# FPGA_7A35T_POWER.net
KiCad netlist of a schematic drawn in Altium Designer
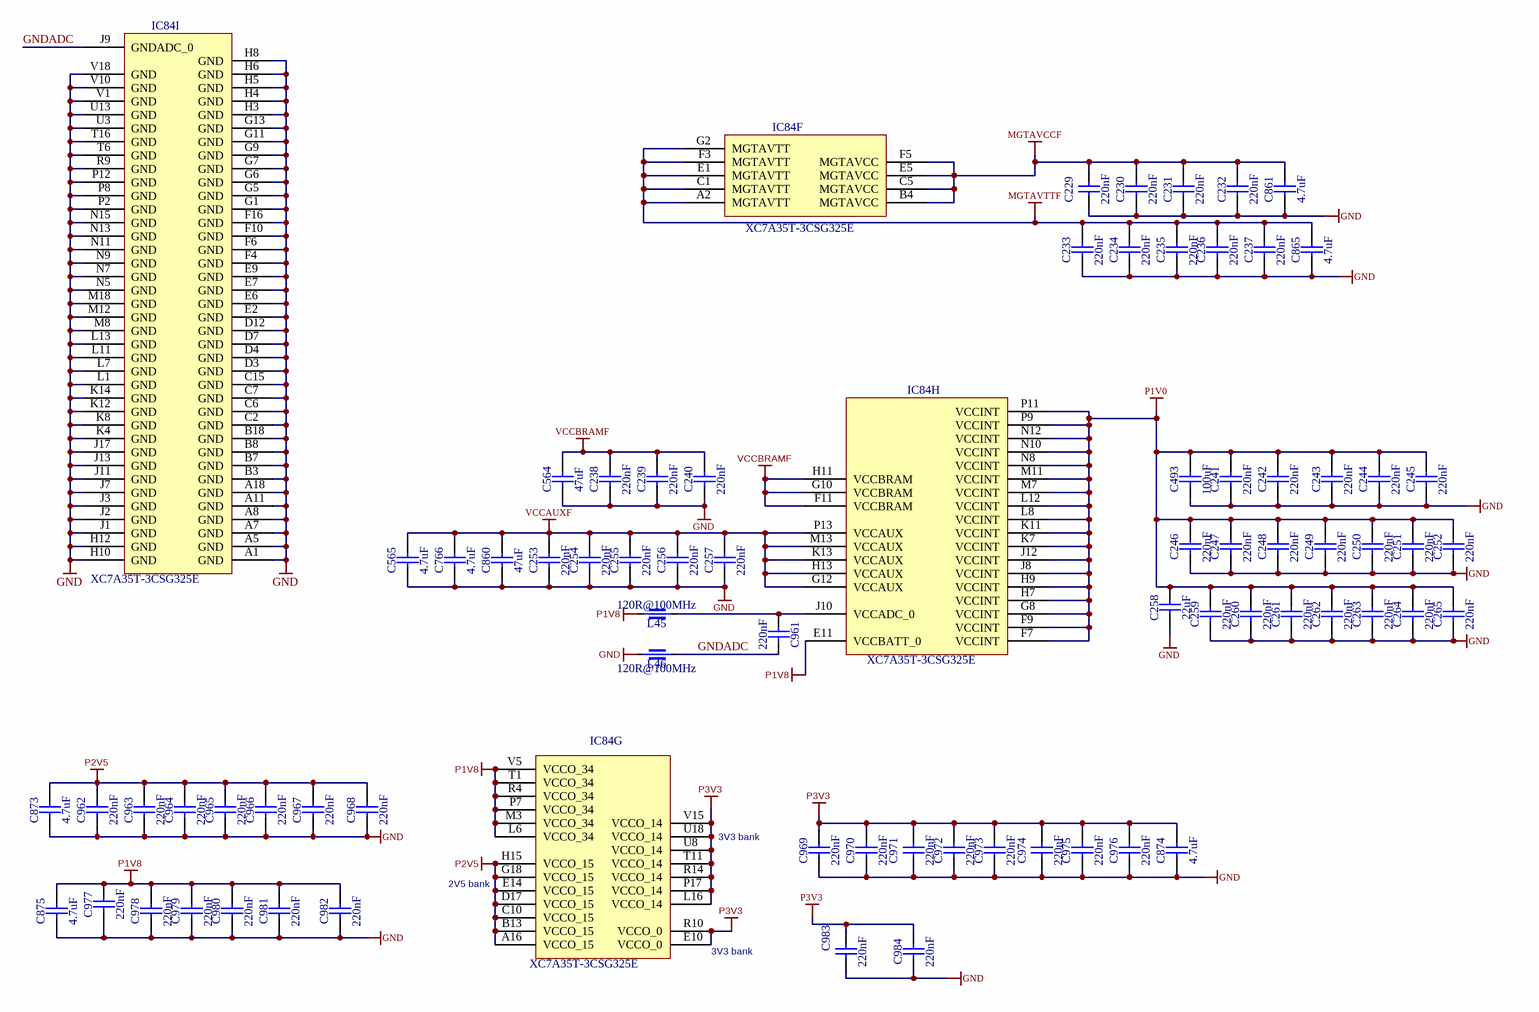
[diagram p0: FPGA_7A35T_POWER.SchDoc]

(export (version "E")
  (design (tool "Eeschema 10.0.6"))
  (components
    (comp (ref "C229")
      (value "220nF")
      (footprint "CAPC0603X33N")
      (description "Non-polarised capacitor")
      (fields
        (field (name "MANUFACTURER PART NUMBER") "CC0201_220NF_6.3V_20%_X5R")
        (field (name "MANUFACTURER") "GENERIC")
        (field (name "AUTHOR") "CERN DEM JLC")
      )
      (libsource (lib "Capacitors") (part "Capacitor - non polarized"))
    )
    (comp (ref "C230")
      (value "220nF")
      (footprint "CAPC0603X33N")
      (description "Non-polarised capacitor")
      (fields
        (field (name "MANUFACTURER PART NUMBER") "CC0201_220NF_6.3V_20%_X5R")
        (field (name "MANUFACTURER") "GENERIC")
        (field (name "AUTHOR") "CERN DEM JLC")
      )
      (libsource (lib "Capacitors") (part "Capacitor - non polarized"))
    )
    (comp (ref "C231")
      (value "220nF")
      (footprint "CAPC0603X33N")
      (description "Non-polarised capacitor")
      (fields
        (field (name "MANUFACTURER PART NUMBER") "CC0201_220NF_6.3V_20%_X5R")
        (field (name "MANUFACTURER") "GENERIC")
        (field (name "AUTHOR") "CERN DEM JLC")
      )
      (libsource (lib "Capacitors") (part "Capacitor - non polarized"))
    )
    (comp (ref "C232")
      (value "220nF")
      (footprint "CAPC0603X33N")
      (description "Non-polarised capacitor")
      (fields
        (field (name "MANUFACTURER PART NUMBER") "CC0201_220NF_6.3V_20%_X5R")
        (field (name "MANUFACTURER") "GENERIC")
        (field (name "AUTHOR") "CERN DEM JLC")
      )
      (libsource (lib "Capacitors") (part "Capacitor - non polarized"))
    )
    (comp (ref "C233")
      (value "220nF")
      (footprint "CAPC0603X33N")
      (description "Non-polarised capacitor")
      (fields
        (field (name "MANUFACTURER PART NUMBER") "CC0201_220NF_6.3V_20%_X5R")
        (field (name "MANUFACTURER") "GENERIC")
        (field (name "AUTHOR") "CERN DEM JLC")
      )
      (libsource (lib "Capacitors") (part "Capacitor - non polarized"))
    )
    (comp (ref "C234")
      (value "220nF")
      (footprint "CAPC0603X33N")
      (description "Non-polarised capacitor")
      (fields
        (field (name "MANUFACTURER PART NUMBER") "CC0201_220NF_6.3V_20%_X5R")
        (field (name "MANUFACTURER") "GENERIC")
        (field (name "AUTHOR") "CERN DEM JLC")
      )
      (libsource (lib "Capacitors") (part "Capacitor - non polarized"))
    )
    (comp (ref "C235")
      (value "220nF")
      (footprint "CAPC0603X33N")
      (description "Non-polarised capacitor")
      (fields
        (field (name "MANUFACTURER PART NUMBER") "CC0201_220NF_6.3V_20%_X5R")
        (field (name "MANUFACTURER") "GENERIC")
        (field (name "AUTHOR") "CERN DEM JLC")
      )
      (libsource (lib "Capacitors") (part "Capacitor - non polarized"))
    )
    (comp (ref "C236")
      (value "220nF")
      (footprint "CAPC0603X33N")
      (description "Non-polarised capacitor")
      (fields
        (field (name "MANUFACTURER PART NUMBER") "CC0201_220NF_6.3V_20%_X5R")
        (field (name "MANUFACTURER") "GENERIC")
        (field (name "AUTHOR") "CERN DEM JLC")
      )
      (libsource (lib "Capacitors") (part "Capacitor - non polarized"))
    )
    (comp (ref "C237")
      (value "220nF")
      (footprint "CAPC0603X33N")
      (description "Non-polarised capacitor")
      (fields
        (field (name "MANUFACTURER PART NUMBER") "CC0201_220NF_6.3V_20%_X5R")
        (field (name "MANUFACTURER") "GENERIC")
        (field (name "AUTHOR") "CERN DEM JLC")
      )
      (libsource (lib "Capacitors") (part "Capacitor - non polarized"))
    )
    (comp (ref "C238")
      (value "220nF")
      (footprint "CAPC0603X33N")
      (description "Non-polarised capacitor")
      (fields
        (field (name "MANUFACTURER PART NUMBER") "CC0201_220NF_6.3V_20%_X5R")
        (field (name "MANUFACTURER") "GENERIC")
        (field (name "AUTHOR") "CERN DEM JLC")
      )
      (libsource (lib "Capacitors") (part "Capacitor - non polarized"))
    )
    (comp (ref "C239")
      (value "220nF")
      (footprint "CAPC0603X33N")
      (description "Non-polarised capacitor")
      (fields
        (field (name "MANUFACTURER PART NUMBER") "CC0201_220NF_6.3V_20%_X5R")
        (field (name "MANUFACTURER") "GENERIC")
        (field (name "AUTHOR") "CERN DEM JLC")
      )
      (libsource (lib "Capacitors") (part "Capacitor - non polarized"))
    )
    (comp (ref "C240")
      (value "220nF")
      (footprint "CAPC0603X33N")
      (description "Non-polarised capacitor")
      (fields
        (field (name "MANUFACTURER PART NUMBER") "CC0201_220NF_6.3V_20%_X5R")
        (field (name "MANUFACTURER") "GENERIC")
        (field (name "AUTHOR") "CERN DEM JLC")
      )
      (libsource (lib "Capacitors") (part "Capacitor - non polarized"))
    )
    (comp (ref "C241")
      (value "220nF")
      (footprint "CAPC0603X33N")
      (description "Non-polarised capacitor")
      (fields
        (field (name "MANUFACTURER PART NUMBER") "CC0201_220NF_6.3V_20%_X5R")
        (field (name "MANUFACTURER") "GENERIC")
        (field (name "AUTHOR") "CERN DEM JLC")
      )
      (libsource (lib "Capacitors") (part "Capacitor - non polarized"))
    )
    (comp (ref "C242")
      (value "220nF")
      (footprint "CAPC0603X33N")
      (description "Non-polarised capacitor")
      (fields
        (field (name "MANUFACTURER PART NUMBER") "CC0201_220NF_6.3V_20%_X5R")
        (field (name "MANUFACTURER") "GENERIC")
        (field (name "AUTHOR") "CERN DEM JLC")
      )
      (libsource (lib "Capacitors") (part "Capacitor - non polarized"))
    )
    (comp (ref "C243")
      (value "220nF")
      (footprint "CAPC0603X33N")
      (description "Non-polarised capacitor")
      (fields
        (field (name "MANUFACTURER PART NUMBER") "CC0201_220NF_6.3V_20%_X5R")
        (field (name "MANUFACTURER") "GENERIC")
        (field (name "AUTHOR") "CERN DEM JLC")
      )
      (libsource (lib "Capacitors") (part "Capacitor - non polarized"))
    )
    (comp (ref "C244")
      (value "220nF")
      (footprint "CAPC0603X33N")
      (description "Non-polarised capacitor")
      (fields
        (field (name "MANUFACTURER PART NUMBER") "CC0201_220NF_6.3V_20%_X5R")
        (field (name "MANUFACTURER") "GENERIC")
        (field (name "AUTHOR") "CERN DEM JLC")
      )
      (libsource (lib "Capacitors") (part "Capacitor - non polarized"))
    )
    (comp (ref "C245")
      (value "220nF")
      (footprint "CAPC0603X33N")
      (description "Non-polarised capacitor")
      (fields
        (field (name "MANUFACTURER PART NUMBER") "CC0201_220NF_6.3V_20%_X5R")
        (field (name "MANUFACTURER") "GENERIC")
        (field (name "AUTHOR") "CERN DEM JLC")
      )
      (libsource (lib "Capacitors") (part "Capacitor - non polarized"))
    )
    (comp (ref "C246")
      (value "220nF")
      (footprint "CAPC0603X33N")
      (description "Non-polarised capacitor")
      (fields
        (field (name "MANUFACTURER PART NUMBER") "CC0201_220NF_6.3V_20%_X5R")
        (field (name "MANUFACTURER") "GENERIC")
        (field (name "AUTHOR") "CERN DEM JLC")
      )
      (libsource (lib "Capacitors") (part "Capacitor - non polarized"))
    )
    (comp (ref "C247")
      (value "220nF")
      (footprint "CAPC0603X33N")
      (description "Non-polarised capacitor")
      (fields
        (field (name "MANUFACTURER PART NUMBER") "CC0201_220NF_6.3V_20%_X5R")
        (field (name "MANUFACTURER") "GENERIC")
        (field (name "AUTHOR") "CERN DEM JLC")
      )
      (libsource (lib "Capacitors") (part "Capacitor - non polarized"))
    )
    (comp (ref "C248")
      (value "220nF")
      (footprint "CAPC0603X33N")
      (description "Non-polarised capacitor")
      (fields
        (field (name "MANUFACTURER PART NUMBER") "CC0201_220NF_6.3V_20%_X5R")
        (field (name "MANUFACTURER") "GENERIC")
        (field (name "AUTHOR") "CERN DEM JLC")
      )
      (libsource (lib "Capacitors") (part "Capacitor - non polarized"))
    )
    (comp (ref "C249")
      (value "220nF")
      (footprint "CAPC0603X33N")
      (description "Non-polarised capacitor")
      (fields
        (field (name "MANUFACTURER PART NUMBER") "CC0201_220NF_6.3V_20%_X5R")
        (field (name "MANUFACTURER") "GENERIC")
        (field (name "AUTHOR") "CERN DEM JLC")
      )
      (libsource (lib "Capacitors") (part "Capacitor - non polarized"))
    )
    (comp (ref "C250")
      (value "220nF")
      (footprint "CAPC0603X33N")
      (description "Non-polarised capacitor")
      (fields
        (field (name "MANUFACTURER PART NUMBER") "CC0201_220NF_6.3V_20%_X5R")
        (field (name "MANUFACTURER") "GENERIC")
        (field (name "AUTHOR") "CERN DEM JLC")
      )
      (libsource (lib "Capacitors") (part "Capacitor - non polarized"))
    )
    (comp (ref "C251")
      (value "220nF")
      (footprint "CAPC0603X33N")
      (description "Non-polarised capacitor")
      (fields
        (field (name "MANUFACTURER PART NUMBER") "CC0201_220NF_6.3V_20%_X5R")
        (field (name "MANUFACTURER") "GENERIC")
        (field (name "AUTHOR") "CERN DEM JLC")
      )
      (libsource (lib "Capacitors") (part "Capacitor - non polarized"))
    )
    (comp (ref "C252")
      (value "220nF")
      (footprint "CAPC0603X33N")
      (description "Non-polarised capacitor")
      (fields
        (field (name "MANUFACTURER PART NUMBER") "CC0201_220NF_6.3V_20%_X5R")
        (field (name "MANUFACTURER") "GENERIC")
        (field (name "AUTHOR") "CERN DEM JLC")
      )
      (libsource (lib "Capacitors") (part "Capacitor - non polarized"))
    )
    (comp (ref "C253")
      (value "220nF")
      (footprint "CAPC0603X33N")
      (description "Non-polarised capacitor")
      (fields
        (field (name "MANUFACTURER PART NUMBER") "CC0201_220NF_6.3V_20%_X5R")
        (field (name "MANUFACTURER") "GENERIC")
        (field (name "AUTHOR") "CERN DEM JLC")
      )
      (libsource (lib "Capacitors") (part "Capacitor - non polarized"))
    )
    (comp (ref "C254")
      (value "220nF")
      (footprint "CAPC0603X33N")
      (description "Non-polarised capacitor")
      (fields
        (field (name "MANUFACTURER PART NUMBER") "CC0201_220NF_6.3V_20%_X5R")
        (field (name "MANUFACTURER") "GENERIC")
        (field (name "AUTHOR") "CERN DEM JLC")
      )
      (libsource (lib "Capacitors") (part "Capacitor - non polarized"))
    )
    (comp (ref "C255")
      (value "220nF")
      (footprint "CAPC0603X33N")
      (description "Non-polarised capacitor")
      (fields
        (field (name "MANUFACTURER PART NUMBER") "CC0201_220NF_6.3V_20%_X5R")
        (field (name "MANUFACTURER") "GENERIC")
        (field (name "AUTHOR") "CERN DEM JLC")
      )
      (libsource (lib "Capacitors") (part "Capacitor - non polarized"))
    )
    (comp (ref "C256")
      (value "220nF")
      (footprint "CAPC0603X33N")
      (description "Non-polarised capacitor")
      (fields
        (field (name "MANUFACTURER PART NUMBER") "CC0201_220NF_6.3V_20%_X5R")
        (field (name "MANUFACTURER") "GENERIC")
        (field (name "AUTHOR") "CERN DEM JLC")
      )
      (libsource (lib "Capacitors") (part "Capacitor - non polarized"))
    )
    (comp (ref "C257")
      (value "220nF")
      (footprint "CAPC0603X33N")
      (description "Non-polarised capacitor")
      (fields
        (field (name "MANUFACTURER PART NUMBER") "CC0201_220NF_6.3V_20%_X5R")
        (field (name "MANUFACTURER") "GENERIC")
        (field (name "AUTHOR") "CERN DEM JLC")
      )
      (libsource (lib "Capacitors") (part "Capacitor - non polarized"))
    )
    (comp (ref "C258")
      (value "22uF")
      (footprint "CAPC2012X135N")
      (description "Non-polarised capacitor")
      (fields
        (field (name "MANUFACTURER PART NUMBER") "CC0805_22UF_6.3V_20%_X5R")
        (field (name "MANUFACTURER") "GENERIC")
        (field (name "AUTHOR") "CERN DEM JLC")
      )
      (libsource (lib "Capacitors") (part "Capacitor - non polarized"))
    )
    (comp (ref "C259")
      (value "220nF")
      (footprint "CAPC0603X33N")
      (description "Non-polarised capacitor")
      (fields
        (field (name "MANUFACTURER PART NUMBER") "CC0201_220NF_6.3V_20%_X5R")
        (field (name "MANUFACTURER") "GENERIC")
        (field (name "AUTHOR") "CERN DEM JLC")
      )
      (libsource (lib "Capacitors") (part "Capacitor - non polarized"))
    )
    (comp (ref "C260")
      (value "220nF")
      (footprint "CAPC0603X33N")
      (description "Non-polarised capacitor")
      (fields
        (field (name "MANUFACTURER PART NUMBER") "CC0201_220NF_6.3V_20%_X5R")
        (field (name "MANUFACTURER") "GENERIC")
        (field (name "AUTHOR") "CERN DEM JLC")
      )
      (libsource (lib "Capacitors") (part "Capacitor - non polarized"))
    )
    (comp (ref "C261")
      (value "220nF")
      (footprint "CAPC0603X33N")
      (description "Non-polarised capacitor")
      (fields
        (field (name "MANUFACTURER PART NUMBER") "CC0201_220NF_6.3V_20%_X5R")
        (field (name "MANUFACTURER") "GENERIC")
        (field (name "AUTHOR") "CERN DEM JLC")
      )
      (libsource (lib "Capacitors") (part "Capacitor - non polarized"))
    )
    (comp (ref "C262")
      (value "220nF")
      (footprint "CAPC0603X33N")
      (description "Non-polarised capacitor")
      (fields
        (field (name "MANUFACTURER PART NUMBER") "CC0201_220NF_6.3V_20%_X5R")
        (field (name "MANUFACTURER") "GENERIC")
        (field (name "AUTHOR") "CERN DEM JLC")
      )
      (libsource (lib "Capacitors") (part "Capacitor - non polarized"))
    )
    (comp (ref "C263")
      (value "220nF")
      (footprint "CAPC0603X33N")
      (description "Non-polarised capacitor")
      (fields
        (field (name "MANUFACTURER PART NUMBER") "CC0201_220NF_6.3V_20%_X5R")
        (field (name "MANUFACTURER") "GENERIC")
        (field (name "AUTHOR") "CERN DEM JLC")
      )
      (libsource (lib "Capacitors") (part "Capacitor - non polarized"))
    )
    (comp (ref "C264")
      (value "220nF")
      (footprint "CAPC0603X33N")
      (description "Non-polarised capacitor")
      (fields
        (field (name "MANUFACTURER PART NUMBER") "CC0201_220NF_6.3V_20%_X5R")
        (field (name "MANUFACTURER") "GENERIC")
        (field (name "AUTHOR") "CERN DEM JLC")
      )
      (libsource (lib "Capacitors") (part "Capacitor - non polarized"))
    )
    (comp (ref "C265")
      (value "220nF")
      (footprint "CAPC0603X33N")
      (description "Non-polarised capacitor")
      (fields
        (field (name "MANUFACTURER PART NUMBER") "CC0201_220NF_6.3V_20%_X5R")
        (field (name "MANUFACTURER") "GENERIC")
        (field (name "AUTHOR") "CERN DEM JLC")
      )
      (libsource (lib "Capacitors") (part "Capacitor - non polarized"))
    )
    (comp (ref "C493")
      (value "100uF")
      (footprint "CAPC3225X270N")
      (description "Non-polarised capacitor")
      (fields
        (field (name "VOLTAGE") "6.3V")
        (field (name "TOLERANCE") "±20%")
        (field (name "AUTHOR") "CERN DEM JLC")
      )
      (libsource (lib "Capacitors") (part "Capacitor - non polarized"))
    )
    (comp (ref "C564")
      (value "47uF")
      (footprint "CAPC1608X100N")
      (description "Non-polarised capacitor")
      (fields
        (field (name "VOLTAGE") "6.3V")
        (field (name "TOLERANCE") "±20%")
        (field (name "AUTHOR") "CERN DEM JLC")
      )
      (libsource (lib "Capacitors") (part "Capacitor - non polarized"))
    )
    (comp (ref "C565")
      (value "4.7uF")
      (footprint "CAPC1005X55N")
      (description "Non-polarised capacitor")
      (fields
        (field (name "VOLTAGE") "6.3V")
        (field (name "TOLERANCE") "±20%")
        (field (name "AUTHOR") "CERN DEM JLC")
      )
      (libsource (lib "Capacitors") (part "Capacitor - non polarized"))
    )
    (comp (ref "C766")
      (value "4.7uF")
      (footprint "CAPC1005X55N")
      (description "Non-polarised capacitor")
      (fields
        (field (name "VOLTAGE") "6.3V")
        (field (name "TOLERANCE") "±20%")
        (field (name "AUTHOR") "CERN DEM JLC")
      )
      (libsource (lib "Capacitors") (part "Capacitor - non polarized"))
    )
    (comp (ref "C860")
      (value "47uF")
      (footprint "CAPC1608X100N")
      (description "Non-polarised capacitor")
      (fields
        (field (name "VOLTAGE") "6.3V")
        (field (name "TOLERANCE") "±20%")
        (field (name "AUTHOR") "CERN DEM JLC")
      )
      (libsource (lib "Capacitors") (part "Capacitor - non polarized"))
    )
    (comp (ref "C861")
      (value "4.7uF")
      (footprint "CAPC1005X55N")
      (description "Non-polarised capacitor")
      (fields
        (field (name "VOLTAGE") "6.3V")
        (field (name "TOLERANCE") "±20%")
        (field (name "AUTHOR") "CERN DEM JLC")
      )
      (libsource (lib "Capacitors") (part "Capacitor - non polarized"))
    )
    (comp (ref "C865")
      (value "4.7uF")
      (footprint "CAPC1005X55N")
      (description "Non-polarised capacitor")
      (fields
        (field (name "VOLTAGE") "6.3V")
        (field (name "TOLERANCE") "±20%")
        (field (name "AUTHOR") "CERN DEM JLC")
      )
      (libsource (lib "Capacitors") (part "Capacitor - non polarized"))
    )
    (comp (ref "C873")
      (value "4.7uF")
      (footprint "CAPC1005X55N")
      (description "Non-polarised capacitor")
      (fields
        (field (name "VOLTAGE") "6.3V")
        (field (name "TOLERANCE") "±20%")
        (field (name "AUTHOR") "CERN DEM JLC")
      )
      (libsource (lib "Capacitors") (part "Capacitor - non polarized"))
    )
    (comp (ref "C874")
      (value "4.7uF")
      (footprint "CAPC1005X55N")
      (description "Non-polarised capacitor")
      (fields
        (field (name "VOLTAGE") "6.3V")
        (field (name "TOLERANCE") "±20%")
        (field (name "AUTHOR") "CERN DEM JLC")
      )
      (libsource (lib "Capacitors") (part "Capacitor - non polarized"))
    )
    (comp (ref "C875")
      (value "4.7uF")
      (footprint "CAPC1005X55N")
      (description "Non-polarised capacitor")
      (fields
        (field (name "VOLTAGE") "6.3V")
        (field (name "TOLERANCE") "±20%")
        (field (name "AUTHOR") "CERN DEM JLC")
      )
      (libsource (lib "Capacitors") (part "Capacitor - non polarized"))
    )
    (comp (ref "C961")
      (value "220nF")
      (footprint "CAPC0603X33N")
      (description "Non-polarised capacitor")
      (fields
        (field (name "MANUFACTURER PART NUMBER") "CC0201_220NF_6.3V_20%_X5R")
        (field (name "MANUFACTURER") "GENERIC")
        (field (name "AUTHOR") "CERN DEM JLC")
      )
      (libsource (lib "Capacitors") (part "Capacitor - non polarized"))
    )
    (comp (ref "C962")
      (value "220nF")
      (footprint "CAPC0603X33N")
      (description "Non-polarised capacitor")
      (fields
        (field (name "MANUFACTURER PART NUMBER") "CC0201_220NF_6.3V_20%_X5R")
        (field (name "MANUFACTURER") "GENERIC")
        (field (name "AUTHOR") "CERN DEM JLC")
      )
      (libsource (lib "Capacitors") (part "Capacitor - non polarized"))
    )
    (comp (ref "C963")
      (value "220nF")
      (footprint "CAPC0603X33N")
      (description "Non-polarised capacitor")
      (fields
        (field (name "MANUFACTURER PART NUMBER") "CC0201_220NF_6.3V_20%_X5R")
        (field (name "MANUFACTURER") "GENERIC")
        (field (name "AUTHOR") "CERN DEM JLC")
      )
      (libsource (lib "Capacitors") (part "Capacitor - non polarized"))
    )
    (comp (ref "C964")
      (value "220nF")
      (footprint "CAPC0603X33N")
      (description "Non-polarised capacitor")
      (fields
        (field (name "MANUFACTURER PART NUMBER") "CC0201_220NF_6.3V_20%_X5R")
        (field (name "MANUFACTURER") "GENERIC")
        (field (name "AUTHOR") "CERN DEM JLC")
      )
      (libsource (lib "Capacitors") (part "Capacitor - non polarized"))
    )
    (comp (ref "C965")
      (value "220nF")
      (footprint "CAPC0603X33N")
      (description "Non-polarised capacitor")
      (fields
        (field (name "MANUFACTURER PART NUMBER") "CC0201_220NF_6.3V_20%_X5R")
        (field (name "MANUFACTURER") "GENERIC")
        (field (name "AUTHOR") "CERN DEM JLC")
      )
      (libsource (lib "Capacitors") (part "Capacitor - non polarized"))
    )
    (comp (ref "C966")
      (value "220nF")
      (footprint "CAPC0603X33N")
      (description "Non-polarised capacitor")
      (fields
        (field (name "MANUFACTURER PART NUMBER") "CC0201_220NF_6.3V_20%_X5R")
        (field (name "MANUFACTURER") "GENERIC")
        (field (name "AUTHOR") "CERN DEM JLC")
      )
      (libsource (lib "Capacitors") (part "Capacitor - non polarized"))
    )
    (comp (ref "C967")
      (value "220nF")
      (footprint "CAPC0603X33N")
      (description "Non-polarised capacitor")
      (fields
        (field (name "MANUFACTURER PART NUMBER") "CC0201_220NF_6.3V_20%_X5R")
        (field (name "MANUFACTURER") "GENERIC")
        (field (name "AUTHOR") "CERN DEM JLC")
      )
      (libsource (lib "Capacitors") (part "Capacitor - non polarized"))
    )
    (comp (ref "C968")
      (value "220nF")
      (footprint "CAPC0603X33N")
      (description "Non-polarised capacitor")
      (fields
        (field (name "MANUFACTURER PART NUMBER") "CC0201_220NF_6.3V_20%_X5R")
        (field (name "MANUFACTURER") "GENERIC")
        (field (name "AUTHOR") "CERN DEM JLC")
      )
      (libsource (lib "Capacitors") (part "Capacitor - non polarized"))
    )
    (comp (ref "C969")
      (value "220nF")
      (footprint "CAPC0603X33N")
      (description "Non-polarised capacitor")
      (fields
        (field (name "MANUFACTURER PART NUMBER") "CC0201_220NF_6.3V_20%_X5R")
        (field (name "MANUFACTURER") "GENERIC")
        (field (name "AUTHOR") "CERN DEM JLC")
      )
      (libsource (lib "Capacitors") (part "Capacitor - non polarized"))
    )
    (comp (ref "C970")
      (value "220nF")
      (footprint "CAPC0603X33N")
      (description "Non-polarised capacitor")
      (fields
        (field (name "MANUFACTURER PART NUMBER") "CC0201_220NF_6.3V_20%_X5R")
        (field (name "MANUFACTURER") "GENERIC")
        (field (name "AUTHOR") "CERN DEM JLC")
      )
      (libsource (lib "Capacitors") (part "Capacitor - non polarized"))
    )
    (comp (ref "C971")
      (value "220nF")
      (footprint "CAPC0603X33N")
      (description "Non-polarised capacitor")
      (fields
        (field (name "MANUFACTURER PART NUMBER") "CC0201_220NF_6.3V_20%_X5R")
        (field (name "MANUFACTURER") "GENERIC")
        (field (name "AUTHOR") "CERN DEM JLC")
      )
      (libsource (lib "Capacitors") (part "Capacitor - non polarized"))
    )
    (comp (ref "C972")
      (value "220nF")
      (footprint "CAPC0603X33N")
      (description "Non-polarised capacitor")
      (fields
        (field (name "MANUFACTURER PART NUMBER") "CC0201_220NF_6.3V_20%_X5R")
        (field (name "MANUFACTURER") "GENERIC")
        (field (name "AUTHOR") "CERN DEM JLC")
      )
      (libsource (lib "Capacitors") (part "Capacitor - non polarized"))
    )
    (comp (ref "C973")
      (value "220nF")
      (footprint "CAPC0603X33N")
      (description "Non-polarised capacitor")
      (fields
        (field (name "MANUFACTURER PART NUMBER") "CC0201_220NF_6.3V_20%_X5R")
        (field (name "MANUFACTURER") "GENERIC")
        (field (name "AUTHOR") "CERN DEM JLC")
      )
      (libsource (lib "Capacitors") (part "Capacitor - non polarized"))
    )
    (comp (ref "C974")
      (value "220nF")
      (footprint "CAPC0603X33N")
      (description "Non-polarised capacitor")
      (fields
        (field (name "MANUFACTURER PART NUMBER") "CC0201_220NF_6.3V_20%_X5R")
        (field (name "MANUFACTURER") "GENERIC")
        (field (name "AUTHOR") "CERN DEM JLC")
      )
      (libsource (lib "Capacitors") (part "Capacitor - non polarized"))
    )
    (comp (ref "C975")
      (value "220nF")
      (footprint "CAPC0603X33N")
      (description "Non-polarised capacitor")
      (fields
        (field (name "MANUFACTURER PART NUMBER") "CC0201_220NF_6.3V_20%_X5R")
        (field (name "MANUFACTURER") "GENERIC")
        (field (name "AUTHOR") "CERN DEM JLC")
      )
      (libsource (lib "Capacitors") (part "Capacitor - non polarized"))
    )
    (comp (ref "C976")
      (value "220nF")
      (footprint "CAPC0603X33N")
      (description "Non-polarised capacitor")
      (fields
        (field (name "MANUFACTURER PART NUMBER") "CC0201_220NF_6.3V_20%_X5R")
        (field (name "MANUFACTURER") "GENERIC")
        (field (name "AUTHOR") "CERN DEM JLC")
      )
      (libsource (lib "Capacitors") (part "Capacitor - non polarized"))
    )
    (comp (ref "C977")
      (value "220nF")
      (footprint "CAPC0603X33N")
      (description "Non-polarised capacitor")
      (fields
        (field (name "MANUFACTURER PART NUMBER") "CC0201_220NF_6.3V_20%_X5R")
        (field (name "MANUFACTURER") "GENERIC")
        (field (name "AUTHOR") "CERN DEM JLC")
      )
      (libsource (lib "Capacitors") (part "Capacitor - non polarized"))
    )
    (comp (ref "C978")
      (value "220nF")
      (footprint "CAPC0603X33N")
      (description "Non-polarised capacitor")
      (fields
        (field (name "MANUFACTURER PART NUMBER") "CC0201_220NF_6.3V_20%_X5R")
        (field (name "MANUFACTURER") "GENERIC")
        (field (name "AUTHOR") "CERN DEM JLC")
      )
      (libsource (lib "Capacitors") (part "Capacitor - non polarized"))
    )
    (comp (ref "C979")
      (value "220nF")
      (footprint "CAPC0603X33N")
      (description "Non-polarised capacitor")
      (fields
        (field (name "MANUFACTURER PART NUMBER") "CC0201_220NF_6.3V_20%_X5R")
        (field (name "MANUFACTURER") "GENERIC")
        (field (name "AUTHOR") "CERN DEM JLC")
      )
      (libsource (lib "Capacitors") (part "Capacitor - non polarized"))
    )
    (comp (ref "C980")
      (value "220nF")
      (footprint "CAPC0603X33N")
      (description "Non-polarised capacitor")
      (fields
        (field (name "MANUFACTURER PART NUMBER") "CC0201_220NF_6.3V_20%_X5R")
        (field (name "MANUFACTURER") "GENERIC")
        (field (name "AUTHOR") "CERN DEM JLC")
      )
      (libsource (lib "Capacitors") (part "Capacitor - non polarized"))
    )
    (comp (ref "C981")
      (value "220nF")
      (footprint "CAPC0603X33N")
      (description "Non-polarised capacitor")
      (fields
        (field (name "MANUFACTURER PART NUMBER") "CC0201_220NF_6.3V_20%_X5R")
        (field (name "MANUFACTURER") "GENERIC")
        (field (name "AUTHOR") "CERN DEM JLC")
      )
      (libsource (lib "Capacitors") (part "Capacitor - non polarized"))
    )
    (comp (ref "C982")
      (value "220nF")
      (footprint "CAPC0603X33N")
      (description "Non-polarised capacitor")
      (fields
        (field (name "MANUFACTURER PART NUMBER") "CC0201_220NF_6.3V_20%_X5R")
        (field (name "MANUFACTURER") "GENERIC")
        (field (name "AUTHOR") "CERN DEM JLC")
      )
      (libsource (lib "Capacitors") (part "Capacitor - non polarized"))
    )
    (comp (ref "C983")
      (value "220nF")
      (footprint "CAPC0603X33N")
      (description "Non-polarised capacitor")
      (fields
        (field (name "MANUFACTURER PART NUMBER") "CC0201_220NF_6.3V_20%_X5R")
        (field (name "MANUFACTURER") "GENERIC")
        (field (name "AUTHOR") "CERN DEM JLC")
      )
      (libsource (lib "Capacitors") (part "Capacitor - non polarized"))
    )
    (comp (ref "C984")
      (value "220nF")
      (footprint "CAPC0603X33N")
      (description "Non-polarised capacitor")
      (fields
        (field (name "MANUFACTURER PART NUMBER") "CC0201_220NF_6.3V_20%_X5R")
        (field (name "MANUFACTURER") "GENERIC")
        (field (name "AUTHOR") "CERN DEM JLC")
      )
      (libsource (lib "Capacitors") (part "Capacitor - non polarized"))
    )
    (comp (ref "IC84")
      (value "XC7A35T-3CSG325E")
      (footprint "CSG325")
      (description "Artix-7 FPGA, 150 User I/Os, 4 GTP, 324-Ball BGA, Speed Grade 3, Extended Grade, Pb-Free")
      (fields (field (name "MANUFACTURER") "Xilinx"))
      (libsource (lib "Altium Content Vault") (part "XLNX-XC7A35T-CSG325"))
    )
    (comp (ref "L45")
      (value "120R@100MHz")
      (footprint "INDC1005X55N")
      (fields
        (field (name "MANUFACTURER PART NUMBER") "BLM15PX121SN1D")
        (field (name "MANUFACTURER") "MURATA")
        (field (name "PART NUMBER") "IND0402_MURATA_BLM15PX121SN1D")
        (field (name "AUTHOR") "CERN DEM JMW")
      )
      (libsource (lib "Inductors & Transformers") (part "Ferrite Bead"))
    )
    (comp (ref "L46")
      (value "120R@100MHz")
      (footprint "INDC1005X55N")
      (fields
        (field (name "MANUFACTURER PART NUMBER") "BLM15PX121SN1D")
        (field (name "MANUFACTURER") "MURATA")
        (field (name "PART NUMBER") "IND0402_MURATA_BLM15PX121SN1D")
        (field (name "AUTHOR") "CERN DEM JMW")
      )
      (libsource (lib "Inductors & Transformers") (part "Ferrite Bead"))
    )
  )
  (nets
    (net (code "1") (name "/GNDADC") (class "Default")
      (node (ref "C961") (pin "2") (pinfunction "2_2") (pintype "passive"))
      (node (ref "IC84") (pin "J9") (pinfunction "GNDADC_0_J9") (pintype "power_in"))
      (node (ref "L46") (pin "2") (pinfunction "2_2") (pintype "passive"))
    )
    (net (code "2") (name "GND") (class "Default")
      (node (ref "C229") (pin "1") (pinfunction "1_1") (pintype "passive"))
      (node (ref "C230") (pin "1") (pinfunction "1_1") (pintype "passive"))
      (node (ref "C231") (pin "1") (pinfunction "1_1") (pintype "passive"))
      (node (ref "C232") (pin "1") (pinfunction "1_1") (pintype "passive"))
      (node (ref "C233") (pin "1") (pinfunction "1_1") (pintype "passive"))
      (node (ref "C234") (pin "1") (pinfunction "1_1") (pintype "passive"))
      (node (ref "C235") (pin "1") (pinfunction "1_1") (pintype "passive"))
      (node (ref "C236") (pin "1") (pinfunction "1_1") (pintype "passive"))
      (node (ref "C237") (pin "1") (pinfunction "1_1") (pintype "passive"))
      (node (ref "C238") (pin "1") (pinfunction "1_1") (pintype "passive"))
      (node (ref "C239") (pin "1") (pinfunction "1_1") (pintype "passive"))
      (node (ref "C240") (pin "1") (pinfunction "1_1") (pintype "passive"))
      (node (ref "C241") (pin "1") (pinfunction "1_1") (pintype "passive"))
      (node (ref "C242") (pin "1") (pinfunction "1_1") (pintype "passive"))
      (node (ref "C243") (pin "1") (pinfunction "1_1") (pintype "passive"))
      (node (ref "C244") (pin "1") (pinfunction "1_1") (pintype "passive"))
      (node (ref "C245") (pin "1") (pinfunction "1_1") (pintype "passive"))
      (node (ref "C246") (pin "1") (pinfunction "1_1") (pintype "passive"))
      (node (ref "C247") (pin "1") (pinfunction "1_1") (pintype "passive"))
      (node (ref "C248") (pin "1") (pinfunction "1_1") (pintype "passive"))
      (node (ref "C249") (pin "1") (pinfunction "1_1") (pintype "passive"))
      (node (ref "C250") (pin "1") (pinfunction "1_1") (pintype "passive"))
      (node (ref "C251") (pin "1") (pinfunction "1_1") (pintype "passive"))
      (node (ref "C252") (pin "1") (pinfunction "1_1") (pintype "passive"))
      (node (ref "C253") (pin "1") (pinfunction "1_1") (pintype "passive"))
      (node (ref "C254") (pin "1") (pinfunction "1_1") (pintype "passive"))
      (node (ref "C255") (pin "1") (pinfunction "1_1") (pintype "passive"))
      (node (ref "C256") (pin "1") (pinfunction "1_1") (pintype "passive"))
      (node (ref "C257") (pin "1") (pinfunction "1_1") (pintype "passive"))
      (node (ref "C258") (pin "1") (pinfunction "1_1") (pintype "passive"))
      (node (ref "C259") (pin "1") (pinfunction "1_1") (pintype "passive"))
      (node (ref "C260") (pin "1") (pinfunction "1_1") (pintype "passive"))
      (node (ref "C261") (pin "1") (pinfunction "1_1") (pintype "passive"))
      (node (ref "C262") (pin "1") (pinfunction "1_1") (pintype "passive"))
      (node (ref "C263") (pin "1") (pinfunction "1_1") (pintype "passive"))
      (node (ref "C264") (pin "1") (pinfunction "1_1") (pintype "passive"))
      (node (ref "C265") (pin "1") (pinfunction "1_1") (pintype "passive"))
      (node (ref "C493") (pin "1") (pinfunction "1_1") (pintype "passive"))
      (node (ref "C564") (pin "1") (pinfunction "1_1") (pintype "passive"))
      (node (ref "C565") (pin "1") (pinfunction "1_1") (pintype "passive"))
      (node (ref "C766") (pin "1") (pinfunction "1_1") (pintype "passive"))
      (node (ref "C860") (pin "1") (pinfunction "1_1") (pintype "passive"))
      (node (ref "C861") (pin "1") (pinfunction "1_1") (pintype "passive"))
      (node (ref "C865") (pin "1") (pinfunction "1_1") (pintype "passive"))
      (node (ref "C873") (pin "1") (pinfunction "1_1") (pintype "passive"))
      (node (ref "C874") (pin "1") (pinfunction "1_1") (pintype "passive"))
      (node (ref "C875") (pin "1") (pinfunction "1_1") (pintype "passive"))
      (node (ref "C962") (pin "1") (pinfunction "1_1") (pintype "passive"))
      (node (ref "C963") (pin "1") (pinfunction "1_1") (pintype "passive"))
      (node (ref "C964") (pin "1") (pinfunction "1_1") (pintype "passive"))
      (node (ref "C965") (pin "1") (pinfunction "1_1") (pintype "passive"))
      (node (ref "C966") (pin "1") (pinfunction "1_1") (pintype "passive"))
      (node (ref "C967") (pin "1") (pinfunction "1_1") (pintype "passive"))
      (node (ref "C968") (pin "1") (pinfunction "1_1") (pintype "passive"))
      (node (ref "C969") (pin "1") (pinfunction "1_1") (pintype "passive"))
      (node (ref "C970") (pin "1") (pinfunction "1_1") (pintype "passive"))
      (node (ref "C971") (pin "1") (pinfunction "1_1") (pintype "passive"))
      (node (ref "C972") (pin "1") (pinfunction "1_1") (pintype "passive"))
      (node (ref "C973") (pin "1") (pinfunction "1_1") (pintype "passive"))
      (node (ref "C974") (pin "1") (pinfunction "1_1") (pintype "passive"))
      (node (ref "C975") (pin "1") (pinfunction "1_1") (pintype "passive"))
      (node (ref "C976") (pin "1") (pinfunction "1_1") (pintype "passive"))
      (node (ref "C977") (pin "1") (pinfunction "1_1") (pintype "passive"))
      (node (ref "C978") (pin "1") (pinfunction "1_1") (pintype "passive"))
      (node (ref "C979") (pin "1") (pinfunction "1_1") (pintype "passive"))
      (node (ref "C980") (pin "1") (pinfunction "1_1") (pintype "passive"))
      (node (ref "C981") (pin "1") (pinfunction "1_1") (pintype "passive"))
      (node (ref "C982") (pin "1") (pinfunction "1_1") (pintype "passive"))
      (node (ref "C983") (pin "1") (pinfunction "1_1") (pintype "passive"))
      (node (ref "C984") (pin "1") (pinfunction "1_1") (pintype "passive"))
      (node (ref "IC84") (pin "A1") (pinfunction "GND_A1") (pintype "power_in"))
      (node (ref "IC84") (pin "A11") (pinfunction "GND_A11") (pintype "power_in"))
      (node (ref "IC84") (pin "A18") (pinfunction "GND_A18") (pintype "power_in"))
      (node (ref "IC84") (pin "A5") (pinfunction "GND_A5") (pintype "power_in"))
      (node (ref "IC84") (pin "A7") (pinfunction "GND_A7") (pintype "power_in"))
      (node (ref "IC84") (pin "A8") (pinfunction "GND_A8") (pintype "power_in"))
      (node (ref "IC84") (pin "B18") (pinfunction "GND_B18") (pintype "power_in"))
      (node (ref "IC84") (pin "B3") (pinfunction "GND_B3") (pintype "power_in"))
      (node (ref "IC84") (pin "B7") (pinfunction "GND_B7") (pintype "power_in"))
      (node (ref "IC84") (pin "B8") (pinfunction "GND_B8") (pintype "power_in"))
      (node (ref "IC84") (pin "C15") (pinfunction "GND_C15") (pintype "power_in"))
      (node (ref "IC84") (pin "C2") (pinfunction "GND_C2") (pintype "power_in"))
      (node (ref "IC84") (pin "C6") (pinfunction "GND_C6") (pintype "power_in"))
      (node (ref "IC84") (pin "C7") (pinfunction "GND_C7") (pintype "power_in"))
      (node (ref "IC84") (pin "D12") (pinfunction "GND_D12") (pintype "power_in"))
      (node (ref "IC84") (pin "D3") (pinfunction "GND_D3") (pintype "power_in"))
      (node (ref "IC84") (pin "D4") (pinfunction "GND_D4") (pintype "power_in"))
      (node (ref "IC84") (pin "D7") (pinfunction "GND_D7") (pintype "power_in"))
      (node (ref "IC84") (pin "E2") (pinfunction "GND_E2") (pintype "power_in"))
      (node (ref "IC84") (pin "E6") (pinfunction "GND_E6") (pintype "power_in"))
      (node (ref "IC84") (pin "E7") (pinfunction "GND_E7") (pintype "power_in"))
      (node (ref "IC84") (pin "E9") (pinfunction "GND_E9") (pintype "power_in"))
      (node (ref "IC84") (pin "F10") (pinfunction "GND_F10") (pintype "power_in"))
      (node (ref "IC84") (pin "F16") (pinfunction "GND_F16") (pintype "power_in"))
      (node (ref "IC84") (pin "F4") (pinfunction "GND_F4") (pintype "power_in"))
      (node (ref "IC84") (pin "F6") (pinfunction "GND_F6") (pintype "power_in"))
      (node (ref "IC84") (pin "G1") (pinfunction "GND_G1") (pintype "power_in"))
      (node (ref "IC84") (pin "G11") (pinfunction "GND_G11") (pintype "power_in"))
      (node (ref "IC84") (pin "G13") (pinfunction "GND_G13") (pintype "power_in"))
      (node (ref "IC84") (pin "G5") (pinfunction "GND_G5") (pintype "power_in"))
      (node (ref "IC84") (pin "G6") (pinfunction "GND_G6") (pintype "power_in"))
      (node (ref "IC84") (pin "G7") (pinfunction "GND_G7") (pintype "power_in"))
      (node (ref "IC84") (pin "G9") (pinfunction "GND_G9") (pintype "power_in"))
      (node (ref "IC84") (pin "H10") (pinfunction "GND_H10") (pintype "power_in"))
      (node (ref "IC84") (pin "H12") (pinfunction "GND_H12") (pintype "power_in"))
      (node (ref "IC84") (pin "H3") (pinfunction "GND_H3") (pintype "power_in"))
      (node (ref "IC84") (pin "H4") (pinfunction "GND_H4") (pintype "power_in"))
      (node (ref "IC84") (pin "H5") (pinfunction "GND_H5") (pintype "power_in"))
      (node (ref "IC84") (pin "H6") (pinfunction "GND_H6") (pintype "power_in"))
      (node (ref "IC84") (pin "H8") (pinfunction "GND_H8") (pintype "power_in"))
      (node (ref "IC84") (pin "J1") (pinfunction "GND_J1") (pintype "power_in"))
      (node (ref "IC84") (pin "J11") (pinfunction "GND_J11") (pintype "power_in"))
      (node (ref "IC84") (pin "J13") (pinfunction "GND_J13") (pintype "power_in"))
      (node (ref "IC84") (pin "J17") (pinfunction "GND_J17") (pintype "power_in"))
      (node (ref "IC84") (pin "J2") (pinfunction "GND_J2") (pintype "power_in"))
      (node (ref "IC84") (pin "J3") (pinfunction "GND_J3") (pintype "power_in"))
      (node (ref "IC84") (pin "J7") (pinfunction "GND_J7") (pintype "power_in"))
      (node (ref "IC84") (pin "K12") (pinfunction "GND_K12") (pintype "power_in"))
      (node (ref "IC84") (pin "K14") (pinfunction "GND_K14") (pintype "power_in"))
      (node (ref "IC84") (pin "K4") (pinfunction "GND_K4") (pintype "power_in"))
      (node (ref "IC84") (pin "K8") (pinfunction "GND_K8") (pintype "power_in"))
      (node (ref "IC84") (pin "L1") (pinfunction "GND_L1") (pintype "power_in"))
      (node (ref "IC84") (pin "L11") (pinfunction "GND_L11") (pintype "power_in"))
      (node (ref "IC84") (pin "L13") (pinfunction "GND_L13") (pintype "power_in"))
      (node (ref "IC84") (pin "L7") (pinfunction "GND_L7") (pintype "power_in"))
      (node (ref "IC84") (pin "M12") (pinfunction "GND_M12") (pintype "power_in"))
      (node (ref "IC84") (pin "M18") (pinfunction "GND_M18") (pintype "power_in"))
      (node (ref "IC84") (pin "M8") (pinfunction "GND_M8") (pintype "power_in"))
      (node (ref "IC84") (pin "N11") (pinfunction "GND_N11") (pintype "power_in"))
      (node (ref "IC84") (pin "N13") (pinfunction "GND_N13") (pintype "power_in"))
      (node (ref "IC84") (pin "N15") (pinfunction "GND_N15") (pintype "power_in"))
      (node (ref "IC84") (pin "N5") (pinfunction "GND_N5") (pintype "power_in"))
      (node (ref "IC84") (pin "N7") (pinfunction "GND_N7") (pintype "power_in"))
      (node (ref "IC84") (pin "N9") (pinfunction "GND_N9") (pintype "power_in"))
      (node (ref "IC84") (pin "P12") (pinfunction "GND_P12") (pintype "power_in"))
      (node (ref "IC84") (pin "P2") (pinfunction "GND_P2") (pintype "power_in"))
      (node (ref "IC84") (pin "P8") (pinfunction "GND_P8") (pintype "power_in"))
      (node (ref "IC84") (pin "R9") (pinfunction "GND_R9") (pintype "power_in"))
      (node (ref "IC84") (pin "T16") (pinfunction "GND_T16") (pintype "power_in"))
      (node (ref "IC84") (pin "T6") (pinfunction "GND_T6") (pintype "power_in"))
      (node (ref "IC84") (pin "U13") (pinfunction "GND_U13") (pintype "power_in"))
      (node (ref "IC84") (pin "U3") (pinfunction "GND_U3") (pintype "power_in"))
      (node (ref "IC84") (pin "V1") (pinfunction "GND_V1") (pintype "power_in"))
      (node (ref "IC84") (pin "V10") (pinfunction "GND_V10") (pintype "power_in"))
      (node (ref "IC84") (pin "V18") (pinfunction "GND_V18") (pintype "power_in"))
      (node (ref "L46") (pin "1") (pinfunction "1_1") (pintype "passive"))
    )
    (net (code "3") (name "MGTAVCCF") (class "Default")
      (node (ref "C229") (pin "2") (pinfunction "2_2") (pintype "passive"))
      (node (ref "C230") (pin "2") (pinfunction "2_2") (pintype "passive"))
      (node (ref "C231") (pin "2") (pinfunction "2_2") (pintype "passive"))
      (node (ref "C232") (pin "2") (pinfunction "2_2") (pintype "passive"))
      (node (ref "C861") (pin "2") (pinfunction "2_2") (pintype "passive"))
      (node (ref "IC84") (pin "B4") (pinfunction "MGTAVCC_B4") (pintype "power_in"))
      (node (ref "IC84") (pin "C5") (pinfunction "MGTAVCC_C5") (pintype "power_in"))
      (node (ref "IC84") (pin "E5") (pinfunction "MGTAVCC_E5") (pintype "power_in"))
      (node (ref "IC84") (pin "F5") (pinfunction "MGTAVCC_F5") (pintype "power_in"))
    )
    (net (code "4") (name "MGTAVTTF") (class "Default")
      (node (ref "C233") (pin "2") (pinfunction "2_2") (pintype "passive"))
      (node (ref "C234") (pin "2") (pinfunction "2_2") (pintype "passive"))
      (node (ref "C235") (pin "2") (pinfunction "2_2") (pintype "passive"))
      (node (ref "C236") (pin "2") (pinfunction "2_2") (pintype "passive"))
      (node (ref "C237") (pin "2") (pinfunction "2_2") (pintype "passive"))
      (node (ref "C865") (pin "2") (pinfunction "2_2") (pintype "passive"))
      (node (ref "IC84") (pin "A2") (pinfunction "MGTAVTT_A2") (pintype "power_in"))
      (node (ref "IC84") (pin "C1") (pinfunction "MGTAVTT_C1") (pintype "power_in"))
      (node (ref "IC84") (pin "E1") (pinfunction "MGTAVTT_E1") (pintype "power_in"))
      (node (ref "IC84") (pin "F3") (pinfunction "MGTAVTT_F3") (pintype "power_in"))
      (node (ref "IC84") (pin "G2") (pinfunction "MGTAVTT_G2") (pintype "power_in"))
    )
    (net (code "5") (name "Net-(IC84H-VCCADC_0)") (class "Default")
      (node (ref "C961") (pin "1") (pinfunction "1_1") (pintype "passive"))
      (node (ref "IC84") (pin "J10") (pinfunction "VCCADC_0_J10") (pintype "power_in"))
      (node (ref "L45") (pin "2") (pinfunction "2_2") (pintype "passive"))
    )
    (net (code "6") (name "P1V0") (class "Default")
      (node (ref "C241") (pin "2") (pinfunction "2_2") (pintype "passive"))
      (node (ref "C242") (pin "2") (pinfunction "2_2") (pintype "passive"))
      (node (ref "C243") (pin "2") (pinfunction "2_2") (pintype "passive"))
      (node (ref "C244") (pin "2") (pinfunction "2_2") (pintype "passive"))
      (node (ref "C245") (pin "2") (pinfunction "2_2") (pintype "passive"))
      (node (ref "C246") (pin "2") (pinfunction "2_2") (pintype "passive"))
      (node (ref "C247") (pin "2") (pinfunction "2_2") (pintype "passive"))
      (node (ref "C248") (pin "2") (pinfunction "2_2") (pintype "passive"))
      (node (ref "C249") (pin "2") (pinfunction "2_2") (pintype "passive"))
      (node (ref "C250") (pin "2") (pinfunction "2_2") (pintype "passive"))
      (node (ref "C251") (pin "2") (pinfunction "2_2") (pintype "passive"))
      (node (ref "C252") (pin "2") (pinfunction "2_2") (pintype "passive"))
      (node (ref "C258") (pin "2") (pinfunction "2_2") (pintype "passive"))
      (node (ref "C259") (pin "2") (pinfunction "2_2") (pintype "passive"))
      (node (ref "C260") (pin "2") (pinfunction "2_2") (pintype "passive"))
      (node (ref "C261") (pin "2") (pinfunction "2_2") (pintype "passive"))
      (node (ref "C262") (pin "2") (pinfunction "2_2") (pintype "passive"))
      (node (ref "C263") (pin "2") (pinfunction "2_2") (pintype "passive"))
      (node (ref "C264") (pin "2") (pinfunction "2_2") (pintype "passive"))
      (node (ref "C265") (pin "2") (pinfunction "2_2") (pintype "passive"))
      (node (ref "C493") (pin "2") (pinfunction "2_2") (pintype "passive"))
      (node (ref "IC84") (pin "F7") (pinfunction "VCCINT_F7") (pintype "power_in"))
      (node (ref "IC84") (pin "F9") (pinfunction "VCCINT_F9") (pintype "power_in"))
      (node (ref "IC84") (pin "G8") (pinfunction "VCCINT_G8") (pintype "power_in"))
      (node (ref "IC84") (pin "H7") (pinfunction "VCCINT_H7") (pintype "power_in"))
      (node (ref "IC84") (pin "H9") (pinfunction "VCCINT_H9") (pintype "power_in"))
      (node (ref "IC84") (pin "J12") (pinfunction "VCCINT_J12") (pintype "power_in"))
      (node (ref "IC84") (pin "J8") (pinfunction "VCCINT_J8") (pintype "power_in"))
      (node (ref "IC84") (pin "K11") (pinfunction "VCCINT_K11") (pintype "power_in"))
      (node (ref "IC84") (pin "K7") (pinfunction "VCCINT_K7") (pintype "power_in"))
      (node (ref "IC84") (pin "L12") (pinfunction "VCCINT_L12") (pintype "power_in"))
      (node (ref "IC84") (pin "L8") (pinfunction "VCCINT_L8") (pintype "power_in"))
      (node (ref "IC84") (pin "M11") (pinfunction "VCCINT_M11") (pintype "power_in"))
      (node (ref "IC84") (pin "M7") (pinfunction "VCCINT_M7") (pintype "power_in"))
      (node (ref "IC84") (pin "N10") (pinfunction "VCCINT_N10") (pintype "power_in"))
      (node (ref "IC84") (pin "N12") (pinfunction "VCCINT_N12") (pintype "power_in"))
      (node (ref "IC84") (pin "N8") (pinfunction "VCCINT_N8") (pintype "power_in"))
      (node (ref "IC84") (pin "P11") (pinfunction "VCCINT_P11") (pintype "power_in"))
      (node (ref "IC84") (pin "P9") (pinfunction "VCCINT_P9") (pintype "power_in"))
    )
    (net (code "7") (name "P1V8") (class "Default")
      (node (ref "C875") (pin "2") (pinfunction "2_2") (pintype "passive"))
      (node (ref "C977") (pin "2") (pinfunction "2_2") (pintype "passive"))
      (node (ref "C978") (pin "2") (pinfunction "2_2") (pintype "passive"))
      (node (ref "C979") (pin "2") (pinfunction "2_2") (pintype "passive"))
      (node (ref "C980") (pin "2") (pinfunction "2_2") (pintype "passive"))
      (node (ref "C981") (pin "2") (pinfunction "2_2") (pintype "passive"))
      (node (ref "C982") (pin "2") (pinfunction "2_2") (pintype "passive"))
      (node (ref "IC84") (pin "E11") (pinfunction "VCCBATT_0_E11") (pintype "power_in"))
      (node (ref "IC84") (pin "L6") (pinfunction "VCCO_34_L6") (pintype "power_in"))
      (node (ref "IC84") (pin "M3") (pinfunction "VCCO_34_M3") (pintype "power_in"))
      (node (ref "IC84") (pin "P7") (pinfunction "VCCO_34_P7") (pintype "power_in"))
      (node (ref "IC84") (pin "R4") (pinfunction "VCCO_34_R4") (pintype "power_in"))
      (node (ref "IC84") (pin "T1") (pinfunction "VCCO_34_T1") (pintype "power_in"))
      (node (ref "IC84") (pin "V5") (pinfunction "VCCO_34_V5") (pintype "power_in"))
      (node (ref "L45") (pin "1") (pinfunction "1_1") (pintype "passive"))
    )
    (net (code "8") (name "P2V5") (class "Default")
      (node (ref "C873") (pin "2") (pinfunction "2_2") (pintype "passive"))
      (node (ref "C962") (pin "2") (pinfunction "2_2") (pintype "passive"))
      (node (ref "C963") (pin "2") (pinfunction "2_2") (pintype "passive"))
      (node (ref "C964") (pin "2") (pinfunction "2_2") (pintype "passive"))
      (node (ref "C965") (pin "2") (pinfunction "2_2") (pintype "passive"))
      (node (ref "C966") (pin "2") (pinfunction "2_2") (pintype "passive"))
      (node (ref "C967") (pin "2") (pinfunction "2_2") (pintype "passive"))
      (node (ref "C968") (pin "2") (pinfunction "2_2") (pintype "passive"))
      (node (ref "IC84") (pin "A16") (pinfunction "VCCO_15_A16") (pintype "power_in"))
      (node (ref "IC84") (pin "B13") (pinfunction "VCCO_15_B13") (pintype "power_in"))
      (node (ref "IC84") (pin "C10") (pinfunction "VCCO_15_C10") (pintype "power_in"))
      (node (ref "IC84") (pin "D17") (pinfunction "VCCO_15_D17") (pintype "power_in"))
      (node (ref "IC84") (pin "E14") (pinfunction "VCCO_15_E14") (pintype "power_in"))
      (node (ref "IC84") (pin "G18") (pinfunction "VCCO_15_G18") (pintype "power_in"))
      (node (ref "IC84") (pin "H15") (pinfunction "VCCO_15_H15") (pintype "power_in"))
    )
    (net (code "9") (name "P3V3") (class "Default")
      (node (ref "C874") (pin "2") (pinfunction "2_2") (pintype "passive"))
      (node (ref "C969") (pin "2") (pinfunction "2_2") (pintype "passive"))
      (node (ref "C970") (pin "2") (pinfunction "2_2") (pintype "passive"))
      (node (ref "C971") (pin "2") (pinfunction "2_2") (pintype "passive"))
      (node (ref "C972") (pin "2") (pinfunction "2_2") (pintype "passive"))
      (node (ref "C973") (pin "2") (pinfunction "2_2") (pintype "passive"))
      (node (ref "C974") (pin "2") (pinfunction "2_2") (pintype "passive"))
      (node (ref "C975") (pin "2") (pinfunction "2_2") (pintype "passive"))
      (node (ref "C976") (pin "2") (pinfunction "2_2") (pintype "passive"))
      (node (ref "C983") (pin "2") (pinfunction "2_2") (pintype "passive"))
      (node (ref "C984") (pin "2") (pinfunction "2_2") (pintype "passive"))
      (node (ref "IC84") (pin "E10") (pinfunction "VCCO_0_E10") (pintype "power_in"))
      (node (ref "IC84") (pin "L16") (pinfunction "VCCO_14_L16") (pintype "power_in"))
      (node (ref "IC84") (pin "P17") (pinfunction "VCCO_14_P17") (pintype "power_in"))
      (node (ref "IC84") (pin "R10") (pinfunction "VCCO_0_R10") (pintype "power_in"))
      (node (ref "IC84") (pin "R14") (pinfunction "VCCO_14_R14") (pintype "power_in"))
      (node (ref "IC84") (pin "T11") (pinfunction "VCCO_14_T11") (pintype "power_in"))
      (node (ref "IC84") (pin "U18") (pinfunction "VCCO_14_U18") (pintype "power_in"))
      (node (ref "IC84") (pin "U8") (pinfunction "VCCO_14_U8") (pintype "power_in"))
      (node (ref "IC84") (pin "V15") (pinfunction "VCCO_14_V15") (pintype "power_in"))
    )
    (net (code "10") (name "VCCAUXF") (class "Default")
      (node (ref "C253") (pin "2") (pinfunction "2_2") (pintype "passive"))
      (node (ref "C254") (pin "2") (pinfunction "2_2") (pintype "passive"))
      (node (ref "C255") (pin "2") (pinfunction "2_2") (pintype "passive"))
      (node (ref "C256") (pin "2") (pinfunction "2_2") (pintype "passive"))
      (node (ref "C257") (pin "2") (pinfunction "2_2") (pintype "passive"))
      (node (ref "C565") (pin "2") (pinfunction "2_2") (pintype "passive"))
      (node (ref "C766") (pin "2") (pinfunction "2_2") (pintype "passive"))
      (node (ref "C860") (pin "2") (pinfunction "2_2") (pintype "passive"))
      (node (ref "IC84") (pin "G12") (pinfunction "VCCAUX_G12") (pintype "power_in"))
      (node (ref "IC84") (pin "H13") (pinfunction "VCCAUX_H13") (pintype "power_in"))
      (node (ref "IC84") (pin "K13") (pinfunction "VCCAUX_K13") (pintype "power_in"))
      (node (ref "IC84") (pin "M13") (pinfunction "VCCAUX_M13") (pintype "power_in"))
      (node (ref "IC84") (pin "P13") (pinfunction "VCCAUX_P13") (pintype "power_in"))
    )
    (net (code "11") (name "VCCBRAMF") (class "Default")
      (node (ref "C238") (pin "2") (pinfunction "2_2") (pintype "passive"))
      (node (ref "C239") (pin "2") (pinfunction "2_2") (pintype "passive"))
      (node (ref "C240") (pin "2") (pinfunction "2_2") (pintype "passive"))
      (node (ref "C564") (pin "2") (pinfunction "2_2") (pintype "passive"))
      (node (ref "IC84") (pin "F11") (pinfunction "VCCBRAM_F11") (pintype "power_in"))
      (node (ref "IC84") (pin "G10") (pinfunction "VCCBRAM_G10") (pintype "power_in"))
      (node (ref "IC84") (pin "H11") (pinfunction "VCCBRAM_H11") (pintype "power_in"))
    )
  )
)
